# SCH.net
KiCad netlist of a schematic drawn in Altium Designer
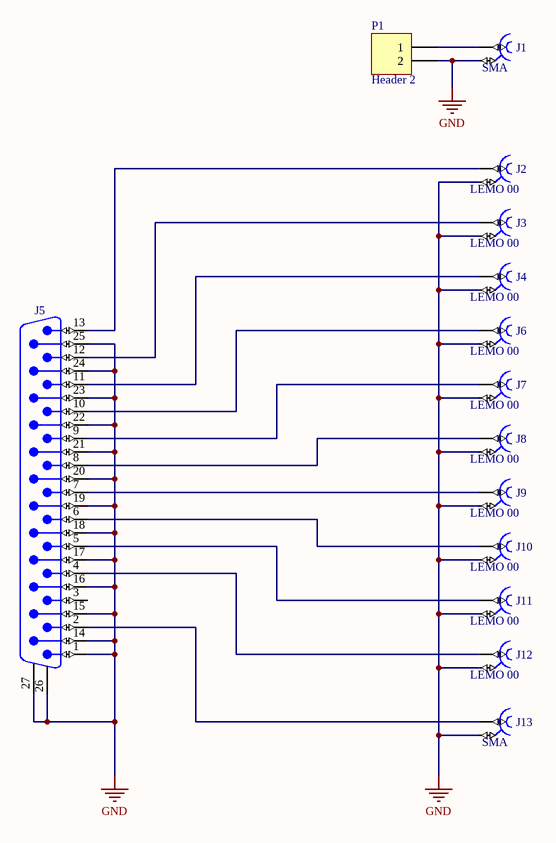
[diagram p0: SCH.SchDoc]

(export (version "E")
  (design (tool "Eeschema 10.0.6"))
  (components
    (comp (ref "J1")
      (value "SMA")
      (footprint "AMPHENOL_132134")
      (fields
        (field (name "PART NUMBER") "AMPHENOL_132134")
        (field (name "MANUFACTURER") "AMPHENOL")
        (field (name "MANUFACTURER PART NUMBER") "132134")
        (field (name "AUTHOR") "CERN DEM JLC")
      )
      (libsource (lib "Connectors") (part "Coax_1Female_1Shield"))
    )
    (comp (ref "J2")
      (value "LEMO 00")
      (footprint "LEMO_EPK.00.250.NTN")
      (fields
        (field (name "PART NUMBER") "LEMO_EPK.00.250.NTN")
        (field (name "MANUFACTURER") "LEMO")
        (field (name "MANUFACTURER PART NUMBER") "EPK.00.250.NTN")
        (field (name "AUTHOR") "CERN DEM JLC")
      )
      (libsource (lib "Connectors") (part "Coax_1Female_1Shield"))
    )
    (comp (ref "J3")
      (value "LEMO 00")
      (footprint "LEMO_EPK.00.250.NTN")
      (fields
        (field (name "PART NUMBER") "LEMO_EPK.00.250.NTN")
        (field (name "MANUFACTURER") "LEMO")
        (field (name "MANUFACTURER PART NUMBER") "EPK.00.250.NTN")
        (field (name "AUTHOR") "CERN DEM JLC")
      )
      (libsource (lib "Connectors") (part "Coax_1Female_1Shield"))
    )
    (comp (ref "J4")
      (value "LEMO 00")
      (footprint "LEMO_EPK.00.250.NTN")
      (fields
        (field (name "PART NUMBER") "LEMO_EPK.00.250.NTN")
        (field (name "MANUFACTURER") "LEMO")
        (field (name "MANUFACTURER PART NUMBER") "EPK.00.250.NTN")
        (field (name "AUTHOR") "CERN DEM JLC")
      )
      (libsource (lib "Connectors") (part "Coax_1Female_1Shield"))
    )
    (comp (ref "J5")
      (value "D-Sub")
      (footprint "TYCO_3-1634582-2")
      (description "Connector D-sub 25 Male")
      (fields
        (field (name "PART NUMBER") "TYCO_3-1634582-2")
        (field (name "MANUFACTURER") "TYCO ELECTRONICS")
        (field (name "AUTHOR") "CERN DEM JLC")
      )
      (libsource (lib "Connectors") (part "Connector D-sub 25 Male"))
    )
    (comp (ref "J6")
      (value "LEMO 00")
      (footprint "LEMO_EPK.00.250.NTN")
      (fields
        (field (name "PART NUMBER") "LEMO_EPK.00.250.NTN")
        (field (name "MANUFACTURER") "LEMO")
        (field (name "MANUFACTURER PART NUMBER") "EPK.00.250.NTN")
        (field (name "AUTHOR") "CERN DEM JLC")
      )
      (libsource (lib "Connectors") (part "Coax_1Female_1Shield"))
    )
    (comp (ref "J7")
      (value "LEMO 00")
      (footprint "LEMO_EPK.00.250.NTN")
      (fields
        (field (name "PART NUMBER") "LEMO_EPK.00.250.NTN")
        (field (name "MANUFACTURER") "LEMO")
        (field (name "MANUFACTURER PART NUMBER") "EPK.00.250.NTN")
        (field (name "AUTHOR") "CERN DEM JLC")
      )
      (libsource (lib "Connectors") (part "Coax_1Female_1Shield"))
    )
    (comp (ref "J8")
      (value "LEMO 00")
      (footprint "LEMO_EPK.00.250.NTN")
      (fields
        (field (name "PART NUMBER") "LEMO_EPK.00.250.NTN")
        (field (name "MANUFACTURER") "LEMO")
        (field (name "MANUFACTURER PART NUMBER") "EPK.00.250.NTN")
        (field (name "AUTHOR") "CERN DEM JLC")
      )
      (libsource (lib "Connectors") (part "Coax_1Female_1Shield"))
    )
    (comp (ref "J9")
      (value "LEMO 00")
      (footprint "LEMO_EPK.00.250.NTN")
      (fields
        (field (name "PART NUMBER") "LEMO_EPK.00.250.NTN")
        (field (name "MANUFACTURER") "LEMO")
        (field (name "MANUFACTURER PART NUMBER") "EPK.00.250.NTN")
        (field (name "AUTHOR") "CERN DEM JLC")
      )
      (libsource (lib "Connectors") (part "Coax_1Female_1Shield"))
    )
    (comp (ref "J10")
      (value "LEMO 00")
      (footprint "LEMO_EPK.00.250.NTN")
      (fields
        (field (name "PART NUMBER") "LEMO_EPK.00.250.NTN")
        (field (name "MANUFACTURER") "LEMO")
        (field (name "MANUFACTURER PART NUMBER") "EPK.00.250.NTN")
        (field (name "AUTHOR") "CERN DEM JLC")
      )
      (libsource (lib "Connectors") (part "Coax_1Female_1Shield"))
    )
    (comp (ref "J11")
      (value "LEMO 00")
      (footprint "LEMO_EPK.00.250.NTN")
      (fields
        (field (name "PART NUMBER") "LEMO_EPK.00.250.NTN")
        (field (name "MANUFACTURER") "LEMO")
        (field (name "MANUFACTURER PART NUMBER") "EPK.00.250.NTN")
        (field (name "AUTHOR") "CERN DEM JLC")
      )
      (libsource (lib "Connectors") (part "Coax_1Female_1Shield"))
    )
    (comp (ref "J12")
      (value "LEMO 00")
      (footprint "LEMO_EPK.00.250.NTN")
      (fields
        (field (name "PART NUMBER") "LEMO_EPK.00.250.NTN")
        (field (name "MANUFACTURER") "LEMO")
        (field (name "MANUFACTURER PART NUMBER") "EPK.00.250.NTN")
        (field (name "AUTHOR") "CERN DEM JLC")
      )
      (libsource (lib "Connectors") (part "Coax_1Female_1Shield"))
    )
    (comp (ref "J13")
      (value "SMA")
      (footprint "AMPHENOL_132134")
      (fields
        (field (name "PART NUMBER") "AMPHENOL_132134")
        (field (name "MANUFACTURER") "AMPHENOL")
        (field (name "MANUFACTURER PART NUMBER") "132134")
        (field (name "AUTHOR") "CERN DEM JLC")
      )
      (libsource (lib "Connectors") (part "Coax_1Female_1Shield"))
    )
    (comp (ref "P1")
      (value "Header 2")
      (footprint "HDR1X2")
      (description "Header, 2-Pin")
      (fields (field (name "PUBLISHER") "Altium Limited"))
      (libsource (lib "Miscellaneous Connectors") (part "Header 2"))
    )
  )
  (nets
    (net (code "1") (name "GND") (class "Default")
      (node (ref "J1") (pin "2") (pinfunction "2_2") (pintype "bidirectional"))
      (node (ref "J10") (pin "2") (pinfunction "2_2") (pintype "bidirectional"))
      (node (ref "J11") (pin "2") (pinfunction "2_2") (pintype "bidirectional"))
      (node (ref "J12") (pin "2") (pinfunction "2_2") (pintype "bidirectional"))
      (node (ref "J13") (pin "2") (pinfunction "2_2") (pintype "bidirectional"))
      (node (ref "J2") (pin "2") (pinfunction "2_2") (pintype "bidirectional"))
      (node (ref "J3") (pin "2") (pinfunction "2_2") (pintype "bidirectional"))
      (node (ref "J4") (pin "2") (pinfunction "2_2") (pintype "bidirectional"))
      (node (ref "J5") (pin "1") (pinfunction "1_1") (pintype "bidirectional"))
      (node (ref "J5") (pin "14") (pinfunction "14_14") (pintype "bidirectional"))
      (node (ref "J5") (pin "15") (pinfunction "15_15") (pintype "bidirectional"))
      (node (ref "J5") (pin "16") (pinfunction "16_16") (pintype "bidirectional"))
      (node (ref "J5") (pin "17") (pinfunction "17_17") (pintype "bidirectional"))
      (node (ref "J5") (pin "18") (pinfunction "18_18") (pintype "bidirectional"))
      (node (ref "J5") (pin "19") (pinfunction "19_19") (pintype "bidirectional"))
      (node (ref "J5") (pin "20") (pinfunction "20_20") (pintype "bidirectional"))
      (node (ref "J5") (pin "21") (pinfunction "21_21") (pintype "bidirectional"))
      (node (ref "J5") (pin "22") (pinfunction "22_22") (pintype "bidirectional"))
      (node (ref "J5") (pin "23") (pinfunction "23_23") (pintype "bidirectional"))
      (node (ref "J5") (pin "24") (pinfunction "24_24") (pintype "bidirectional"))
      (node (ref "J5") (pin "25") (pinfunction "25_25") (pintype "bidirectional"))
      (node (ref "J5") (pin "26") (pinfunction "26_26") (pintype "passive"))
      (node (ref "J5") (pin "27") (pinfunction "27_27") (pintype "passive"))
      (node (ref "J6") (pin "2") (pinfunction "2_2") (pintype "bidirectional"))
      (node (ref "J7") (pin "2") (pinfunction "2_2") (pintype "bidirectional"))
      (node (ref "J8") (pin "2") (pinfunction "2_2") (pintype "bidirectional"))
      (node (ref "J9") (pin "2") (pinfunction "2_2") (pintype "bidirectional"))
      (node (ref "P1") (pin "2") (pinfunction "2_2") (pintype "passive"))
    )
    (net (code "2") (name "Net-(J1-Pad1)") (class "Default")
      (node (ref "J1") (pin "1") (pinfunction "1_1") (pintype "bidirectional"))
      (node (ref "P1") (pin "1") (pinfunction "1_1") (pintype "passive"))
    )
    (net (code "3") (name "Net-(J2-Pad1)") (class "Default")
      (node (ref "J2") (pin "1") (pinfunction "1_1") (pintype "bidirectional"))
      (node (ref "J5") (pin "13") (pinfunction "13_13") (pintype "bidirectional"))
    )
    (net (code "4") (name "Net-(J3-Pad1)") (class "Default")
      (node (ref "J3") (pin "1") (pinfunction "1_1") (pintype "bidirectional"))
      (node (ref "J5") (pin "12") (pinfunction "12_12") (pintype "bidirectional"))
    )
    (net (code "5") (name "Net-(J4-Pad1)") (class "Default")
      (node (ref "J4") (pin "1") (pinfunction "1_1") (pintype "bidirectional"))
      (node (ref "J5") (pin "11") (pinfunction "11_11") (pintype "bidirectional"))
    )
    (net (code "6") (name "Net-(J5-Pad7)") (class "Default")
      (node (ref "J5") (pin "7") (pinfunction "7_7") (pintype "bidirectional"))
      (node (ref "J9") (pin "1") (pinfunction "1_1") (pintype "bidirectional"))
    )
    (net (code "7") (name "Net-(J5-Pad8)") (class "Default")
      (node (ref "J5") (pin "8") (pinfunction "8_8") (pintype "bidirectional"))
      (node (ref "J8") (pin "1") (pinfunction "1_1") (pintype "bidirectional"))
    )
    (net (code "8") (name "Net-(J5-Pad9)") (class "Default")
      (node (ref "J5") (pin "9") (pinfunction "9_9") (pintype "bidirectional"))
      (node (ref "J7") (pin "1") (pinfunction "1_1") (pintype "bidirectional"))
    )
    (net (code "9") (name "Net-(J5-Pad10)") (class "Default")
      (node (ref "J5") (pin "10") (pinfunction "10_10") (pintype "bidirectional"))
      (node (ref "J6") (pin "1") (pinfunction "1_1") (pintype "bidirectional"))
    )
    (net (code "10") (name "Net-(J10-Pad1)") (class "Default")
      (node (ref "J10") (pin "1") (pinfunction "1_1") (pintype "bidirectional"))
      (node (ref "J5") (pin "6") (pinfunction "6_6") (pintype "bidirectional"))
    )
    (net (code "11") (name "Net-(J11-Pad1)") (class "Default")
      (node (ref "J11") (pin "1") (pinfunction "1_1") (pintype "bidirectional"))
      (node (ref "J5") (pin "5") (pinfunction "5_5") (pintype "bidirectional"))
    )
    (net (code "12") (name "Net-(J12-Pad1)") (class "Default")
      (node (ref "J12") (pin "1") (pinfunction "1_1") (pintype "bidirectional"))
      (node (ref "J5") (pin "4") (pinfunction "4_4") (pintype "bidirectional"))
    )
    (net (code "13") (name "Net-(J13-Pad1)") (class "Default")
      (node (ref "J13") (pin "1") (pinfunction "1_1") (pintype "bidirectional"))
      (node (ref "J5") (pin "2") (pinfunction "2_2") (pintype "bidirectional"))
    )
    (net (code "14") (name "unconnected-(J5-Pad3)") (class "Default")
      (node (ref "J5") (pin "3") (pinfunction "3_3") (pintype "bidirectional"))
    )
  )
)
